# CCM_0010.net
KiCad netlist of a schematic drawn in EAGLE
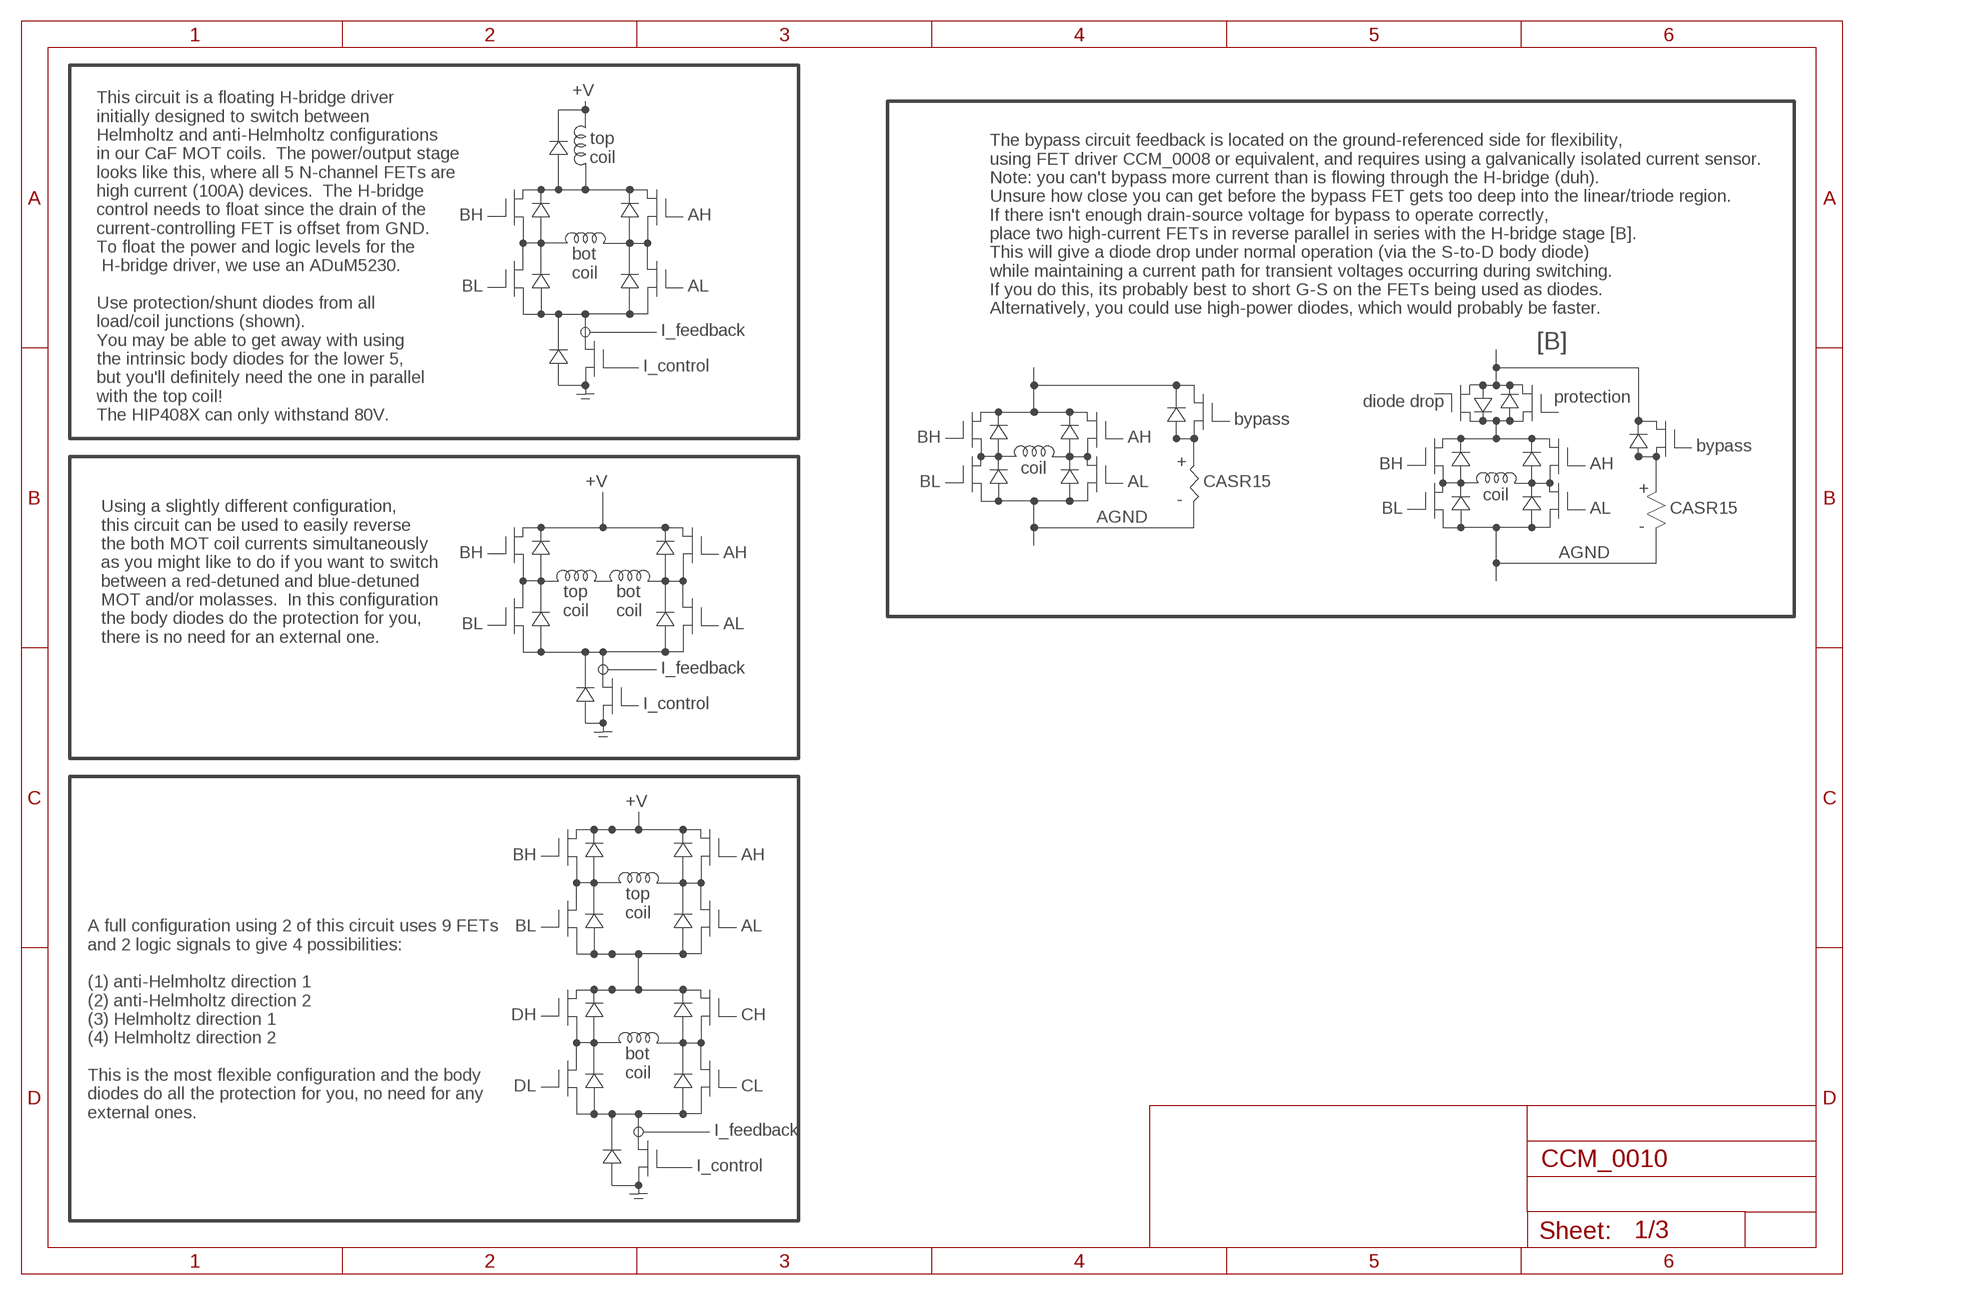
[diagram p0: schematic, sheet 1]
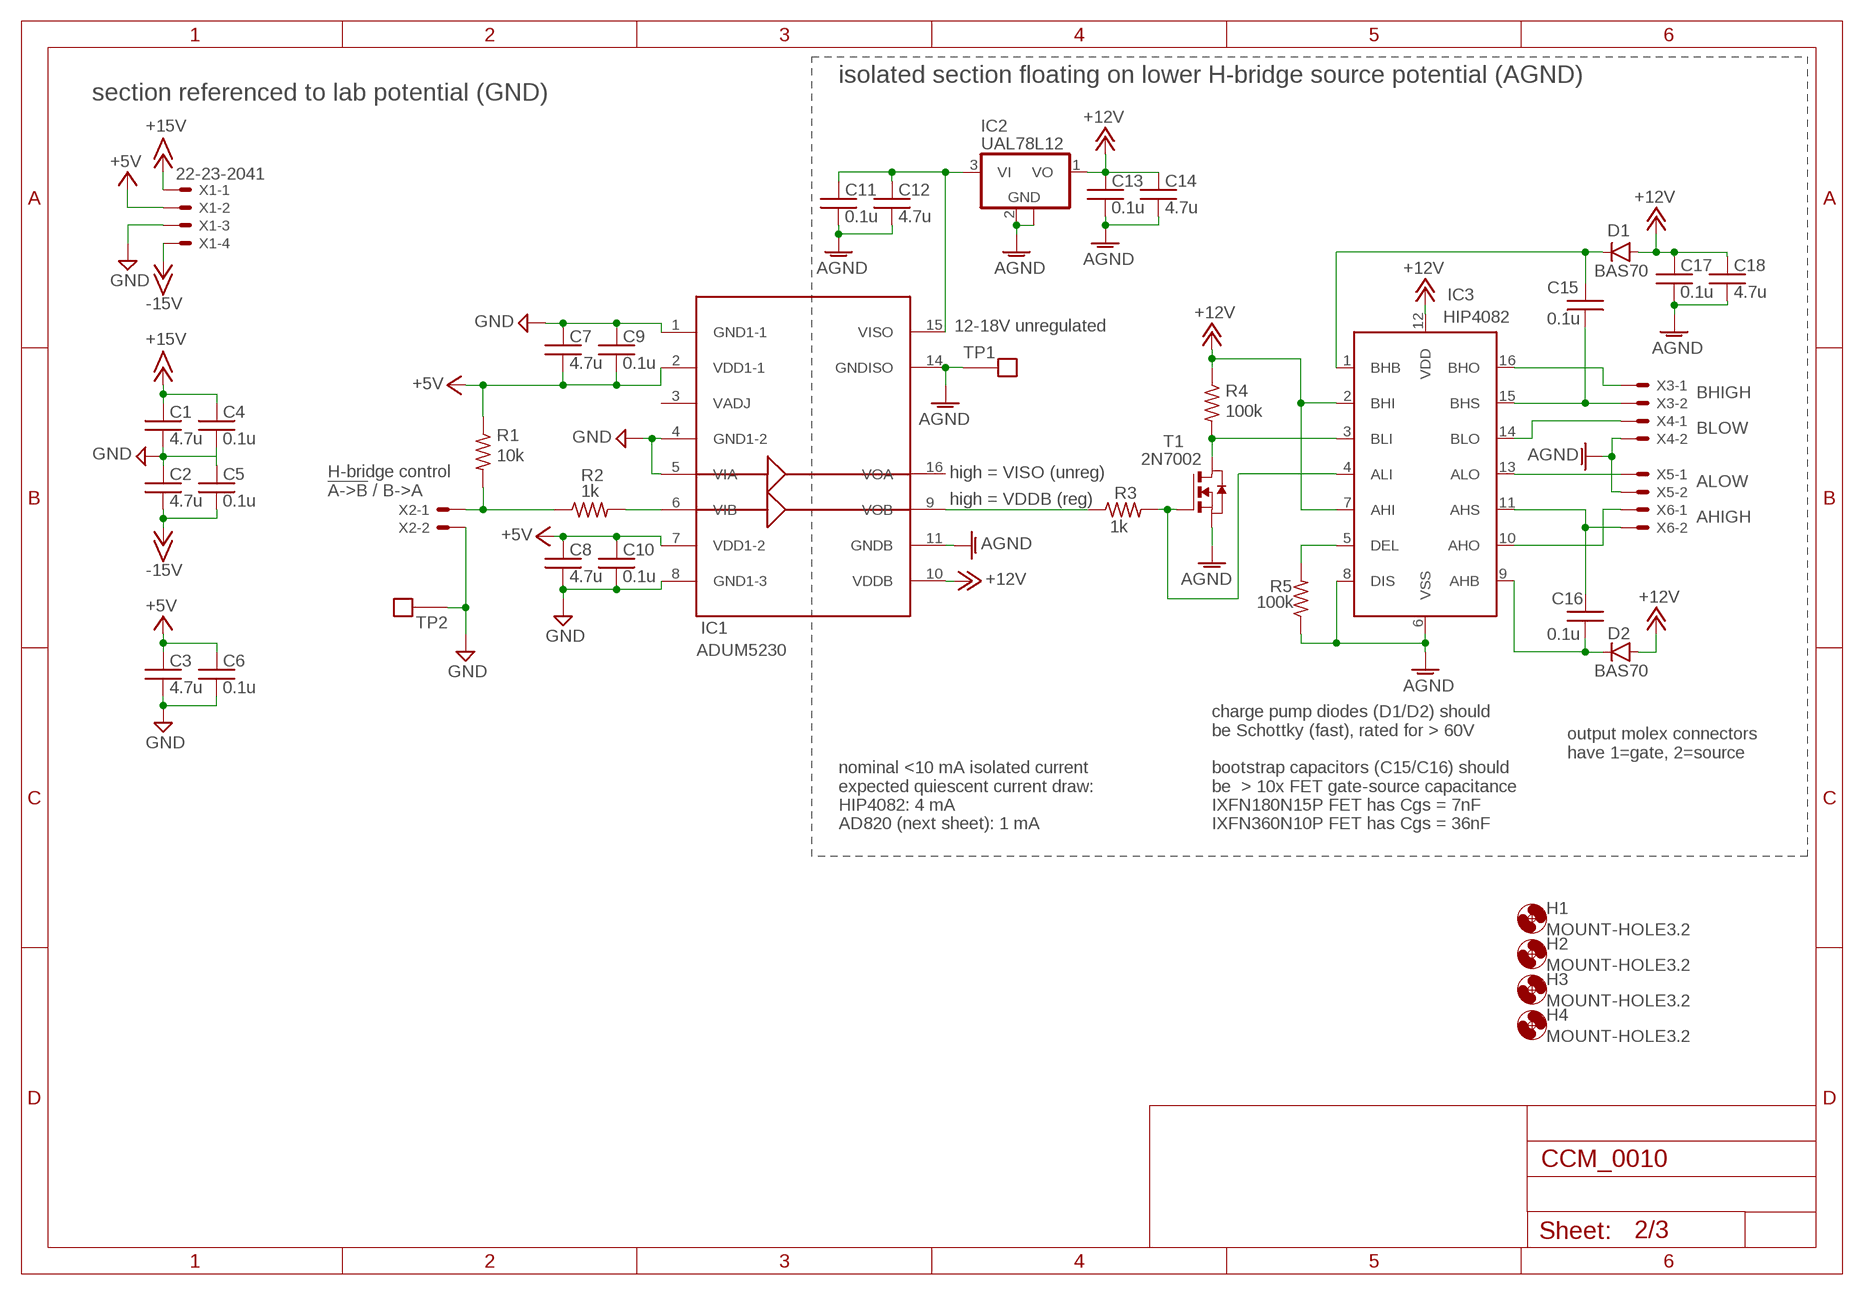
[diagram p1: schematic, sheet 2]
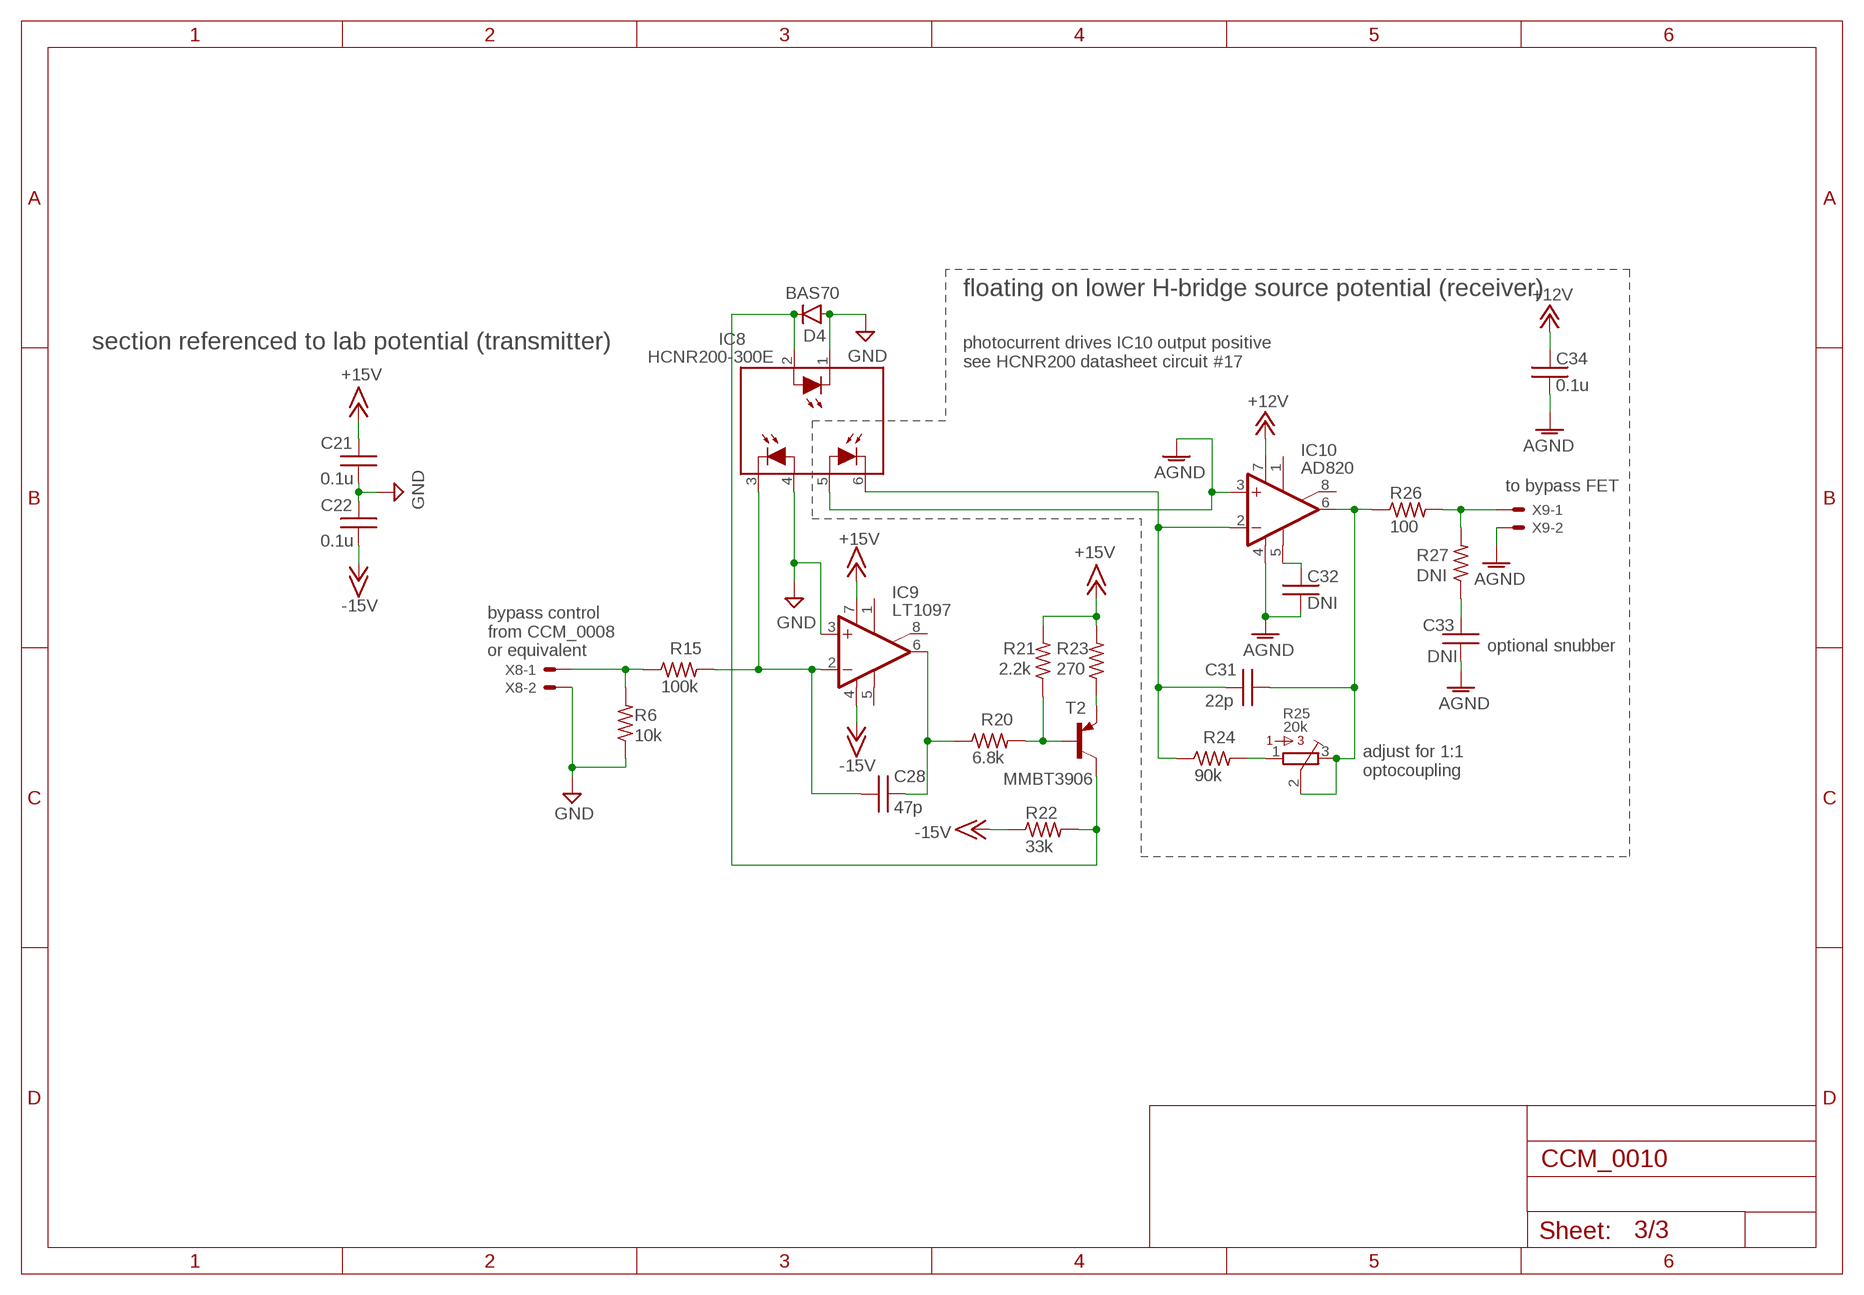
[diagram p2: schematic, sheet 3]

(export (version "E")
  (design (tool "Eeschema 10.0.6"))
  (components
    (comp (ref "C21")
      (value "0.1u")
      (footprint "eagle-import:0603")
      (libsource (lib "eagle-import") (part "C0603"))
    )
    (comp (ref "C22")
      (value "0.1u")
      (footprint "eagle-import:0603")
      (libsource (lib "eagle-import") (part "C0603"))
    )
    (comp (ref "C28")
      (value "47p")
      (footprint "eagle-import:0603")
      (libsource (lib "eagle-import") (part "C0603"))
    )
    (comp (ref "C31")
      (value "22p")
      (footprint "eagle-import:0603")
      (libsource (lib "eagle-import") (part "C0603"))
    )
    (comp (ref "C32")
      (value "DNI")
      (footprint "eagle-import:0603")
      (libsource (lib "eagle-import") (part "C0603"))
    )
    (comp (ref "C33")
      (value "DNI")
      (footprint "eagle-import:0603")
      (libsource (lib "eagle-import") (part "C0603"))
    )
    (comp (ref "C34")
      (value "0.1u")
      (footprint "eagle-import:0603")
      (libsource (lib "eagle-import") (part "C0603"))
    )
    (comp (ref "D4")
      (value "BAS70")
      (footprint "eagle-import:SOT23-3")
      (libsource (lib "eagle-import") (part "DIODESOT23"))
    )
    (comp (ref "IC8")
      (value "HCNR200-300E")
      (footprint "eagle-import:DIP8-400")
      (libsource (lib "eagle-import") (part "HCNR20-300E0"))
    )
    (comp (ref "IC9")
      (value "LT1097")
      (footprint "eagle-import:SO08")
      (libsource (lib "eagle-import") (part "OP07RC"))
    )
    (comp (ref "IC10")
      (value "AD820")
      (footprint "eagle-import:SO08")
      (libsource (lib "eagle-import") (part "OP07RC"))
    )
    (comp (ref "R6")
      (value "10k")
      (footprint "eagle-import:0603")
      (libsource (lib "eagle-import") (part "R0603"))
    )
    (comp (ref "R15")
      (value "100k")
      (footprint "eagle-import:0603")
      (libsource (lib "eagle-import") (part "R0603"))
    )
    (comp (ref "R20")
      (value "6.8k")
      (footprint "eagle-import:0603")
      (libsource (lib "eagle-import") (part "R0603"))
    )
    (comp (ref "R21")
      (value "2.2k")
      (footprint "eagle-import:0603")
      (libsource (lib "eagle-import") (part "R0603"))
    )
    (comp (ref "R22")
      (value "33k")
      (footprint "eagle-import:0603")
      (libsource (lib "eagle-import") (part "R0603"))
    )
    (comp (ref "R23")
      (value "270")
      (footprint "eagle-import:0603")
      (libsource (lib "eagle-import") (part "R0603"))
    )
    (comp (ref "R24")
      (value "90k")
      (footprint "eagle-import:0603")
      (libsource (lib "eagle-import") (part "R0603"))
    )
    (comp (ref "R25")
      (value "20k")
      (footprint "eagle-import:3386W")
      (libsource (lib "eagle-import") (part "3386-W"))
    )
    (comp (ref "R26")
      (value "100")
      (footprint "eagle-import:0603")
      (libsource (lib "eagle-import") (part "R0603"))
    )
    (comp (ref "R27")
      (value "DNI")
      (footprint "eagle-import:0603")
      (libsource (lib "eagle-import") (part "R0603"))
    )
    (comp (ref "T2")
      (value "MMBT3906")
      (footprint "eagle-import:SOT23-BEC")
      (libsource (lib "eagle-import") (part "-PNP-SOT23-BECMMBT3906LT1"))
    )
    (comp (ref "X8")
      (value "22-23-2021")
      (footprint "eagle-import:22-23-2021")
      (fields (field (name "MF") "MOLEX"))
      (libsource (lib "eagle-import") (part "22-23-2021"))
    )
    (comp (ref "X9")
      (value "22-23-2021")
      (footprint "eagle-import:22-23-2021")
      (fields (field (name "MF") "MOLEX"))
      (libsource (lib "eagle-import") (part "22-23-2021"))
    )
    (comp (ref "C1")
      (value "4.7u")
      (footprint "eagle-import:0603")
      (libsource (lib "eagle-import") (part "C0603"))
    )
    (comp (ref "C2")
      (value "4.7u")
      (footprint "eagle-import:0603")
      (libsource (lib "eagle-import") (part "C0603"))
    )
    (comp (ref "C3")
      (value "4.7u")
      (footprint "eagle-import:0603")
      (libsource (lib "eagle-import") (part "C0603"))
    )
    (comp (ref "C4")
      (value "0.1u")
      (footprint "eagle-import:0603")
      (libsource (lib "eagle-import") (part "C0603"))
    )
    (comp (ref "C5")
      (value "0.1u")
      (footprint "eagle-import:0603")
      (libsource (lib "eagle-import") (part "C0603"))
    )
    (comp (ref "C6")
      (value "0.1u")
      (footprint "eagle-import:0603")
      (libsource (lib "eagle-import") (part "C0603"))
    )
    (comp (ref "C7")
      (value "4.7u")
      (footprint "eagle-import:0603")
      (libsource (lib "eagle-import") (part "C0603"))
    )
    (comp (ref "C8")
      (value "4.7u")
      (footprint "eagle-import:0603")
      (libsource (lib "eagle-import") (part "C0603"))
    )
    (comp (ref "C9")
      (value "0.1u")
      (footprint "eagle-import:0603")
      (libsource (lib "eagle-import") (part "C0603"))
    )
    (comp (ref "C10")
      (value "0.1u")
      (footprint "eagle-import:0603")
      (libsource (lib "eagle-import") (part "C0603"))
    )
    (comp (ref "C11")
      (value "0.1u")
      (footprint "eagle-import:0603")
      (libsource (lib "eagle-import") (part "C0603"))
    )
    (comp (ref "C12")
      (value "4.7u")
      (footprint "eagle-import:0603")
      (libsource (lib "eagle-import") (part "C0603"))
    )
    (comp (ref "C13")
      (value "0.1u")
      (footprint "eagle-import:0603")
      (libsource (lib "eagle-import") (part "C0603"))
    )
    (comp (ref "C14")
      (value "4.7u")
      (footprint "eagle-import:0603")
      (libsource (lib "eagle-import") (part "C0603"))
    )
    (comp (ref "C15")
      (value "0.1u")
      (footprint "eagle-import:0603")
      (libsource (lib "eagle-import") (part "C0603"))
    )
    (comp (ref "C16")
      (value "0.1u")
      (footprint "eagle-import:0603")
      (libsource (lib "eagle-import") (part "C0603"))
    )
    (comp (ref "C17")
      (value "0.1u")
      (footprint "eagle-import:0603")
      (libsource (lib "eagle-import") (part "C0603"))
    )
    (comp (ref "C18")
      (value "4.7u")
      (footprint "eagle-import:0603")
      (libsource (lib "eagle-import") (part "C0603"))
    )
    (comp (ref "D1")
      (value "BAS70")
      (footprint "eagle-import:SOT23-3")
      (libsource (lib "eagle-import") (part "DIODESOT23"))
    )
    (comp (ref "D2")
      (value "BAS70")
      (footprint "eagle-import:SOT23-3")
      (libsource (lib "eagle-import") (part "DIODESOT23"))
    )
    (comp (ref "H1")
      (value "MOUNT-HOLE3.2")
      (footprint "eagle-import:3,2")
      (libsource (lib "eagle-import") (part "MOUNT-HOLE3.2"))
    )
    (comp (ref "H2")
      (value "MOUNT-HOLE3.2")
      (footprint "eagle-import:3,2")
      (libsource (lib "eagle-import") (part "MOUNT-HOLE3.2"))
    )
    (comp (ref "H3")
      (value "MOUNT-HOLE3.2")
      (footprint "eagle-import:3,2")
      (libsource (lib "eagle-import") (part "MOUNT-HOLE3.2"))
    )
    (comp (ref "H4")
      (value "MOUNT-HOLE3.2")
      (footprint "eagle-import:3,2")
      (libsource (lib "eagle-import") (part "MOUNT-HOLE3.2"))
    )
    (comp (ref "IC1")
      (value "ADUM5230")
      (footprint "eagle-import:SO16W")
      (libsource (lib "eagle-import") (part "ADUM5230"))
    )
    (comp (ref "IC2")
      (value "UAL78L12")
      (footprint "eagle-import:SOT89")
      (libsource (lib "eagle-import") (part "78LF12"))
    )
    (comp (ref "IC3")
      (value "HIP4082")
      (footprint "eagle-import:SO16")
      (libsource (lib "eagle-import") (part "HIP4082"))
    )
    (comp (ref "R1")
      (value "10k")
      (footprint "eagle-import:0603")
      (libsource (lib "eagle-import") (part "R0603"))
    )
    (comp (ref "R2")
      (value "1k")
      (footprint "eagle-import:0603")
      (libsource (lib "eagle-import") (part "R0603"))
    )
    (comp (ref "R3")
      (value "1k")
      (footprint "eagle-import:0603")
      (libsource (lib "eagle-import") (part "R0603"))
    )
    (comp (ref "R4")
      (value "100k")
      (footprint "eagle-import:0603")
      (libsource (lib "eagle-import") (part "R0603"))
    )
    (comp (ref "R5")
      (value "100k")
      (footprint "eagle-import:0603")
      (libsource (lib "eagle-import") (part "R0603"))
    )
    (comp (ref "T1")
      (value "2N7002")
      (footprint "eagle-import:SOT-23")
      (libsource (lib "eagle-import") (part "NMOSSOT23"))
    )
    (comp (ref "TP1")
      (value "TESTPOINT")
      (footprint "eagle-import:TESTPOINT")
      (libsource (lib "eagle-import") (part "TESTPOINT"))
    )
    (comp (ref "TP2")
      (value "TESTPOINT")
      (footprint "eagle-import:TESTPOINT")
      (libsource (lib "eagle-import") (part "TESTPOINT"))
    )
    (comp (ref "X1")
      (value "22-23-2041")
      (footprint "eagle-import:22-23-2041")
      (fields (field (name "MF") "MOLEX"))
      (libsource (lib "eagle-import") (part "22-23-2041"))
    )
    (comp (ref "X2")
      (value "22-23-2021")
      (footprint "eagle-import:22-23-2021")
      (fields (field (name "MF") "MOLEX"))
      (libsource (lib "eagle-import") (part "22-23-2021"))
    )
    (comp (ref "X3")
      (value "22-23-2021")
      (footprint "eagle-import:22-23-2021")
      (fields (field (name "MF") "MOLEX"))
      (libsource (lib "eagle-import") (part "22-23-2021"))
    )
    (comp (ref "X4")
      (value "22-23-2021")
      (footprint "eagle-import:22-23-2021")
      (fields (field (name "MF") "MOLEX"))
      (libsource (lib "eagle-import") (part "22-23-2021"))
    )
    (comp (ref "X5")
      (value "22-23-2021")
      (footprint "eagle-import:22-23-2021")
      (fields (field (name "MF") "MOLEX"))
      (libsource (lib "eagle-import") (part "22-23-2021"))
    )
    (comp (ref "X6")
      (value "22-23-2021")
      (footprint "eagle-import:22-23-2021")
      (fields (field (name "MF") "MOLEX"))
      (libsource (lib "eagle-import") (part "22-23-2021"))
    )
  )
  (nets
    (net (code "1") (name "+5V") (class "Default")
      (node (ref "C10") (pin "1") (pinfunction "1_1") (pintype "passive"))
      (node (ref "C3") (pin "1") (pinfunction "1_1") (pintype "passive"))
      (node (ref "C6") (pin "1") (pinfunction "1_1") (pintype "passive"))
      (node (ref "C7") (pin "2") (pinfunction "2_2") (pintype "passive"))
      (node (ref "C8") (pin "1") (pinfunction "1_1") (pintype "passive"))
      (node (ref "C9") (pin "2") (pinfunction "2_2") (pintype "passive"))
      (node (ref "IC1") (pin "2") (pinfunction "VDD1-1_2") (pintype "bidirectional"))
      (node (ref "IC1") (pin "7") (pinfunction "VDD1-2_7") (pintype "bidirectional"))
      (node (ref "R1") (pin "1") (pinfunction "1_1") (pintype "passive"))
      (node (ref "X1") (pin "2") (pinfunction "S_2") (pintype "passive"))
    )
    (net (code "2") (name "+12V") (class "Default")
      (node (ref "C13") (pin "1") (pinfunction "1_1") (pintype "passive"))
      (node (ref "C14") (pin "1") (pinfunction "1_1") (pintype "passive"))
      (node (ref "C17") (pin "1") (pinfunction "1_1") (pintype "passive"))
      (node (ref "C18") (pin "1") (pinfunction "1_1") (pintype "passive"))
      (node (ref "C34") (pin "1") (pinfunction "1_1") (pintype "passive"))
      (node (ref "D1") (pin "1") (pinfunction "A_1") (pintype "passive"))
      (node (ref "D2") (pin "1") (pinfunction "A_1") (pintype "passive"))
      (node (ref "IC1") (pin "10") (pinfunction "VDDB_10") (pintype "bidirectional"))
      (node (ref "IC10") (pin "7") (pinfunction "V+_7") (pintype "power_in"))
      (node (ref "IC2") (pin "1") (pinfunction "VO_1") (pintype "passive"))
      (node (ref "IC3") (pin "12") (pinfunction "VDD_12") (pintype "power_in"))
      (node (ref "IC3") (pin "2") (pinfunction "BHI_2") (pintype "input"))
      (node (ref "IC3") (pin "7") (pinfunction "AHI_7") (pintype "input"))
      (node (ref "R4") (pin "1") (pinfunction "1_1") (pintype "passive"))
    )
    (net (code "3") (name "+15V") (class "Default")
      (node (ref "C1") (pin "1") (pinfunction "1_1") (pintype "passive"))
      (node (ref "C21") (pin "2") (pinfunction "2_2") (pintype "passive"))
      (node (ref "C4") (pin "1") (pinfunction "1_1") (pintype "passive"))
      (node (ref "IC9") (pin "7") (pinfunction "V+_7") (pintype "power_in"))
      (node (ref "R21") (pin "2") (pinfunction "2_2") (pintype "passive"))
      (node (ref "R23") (pin "2") (pinfunction "2_2") (pintype "passive"))
      (node (ref "X1") (pin "1") (pinfunction "S_1") (pintype "passive"))
    )
    (net (code "4") (name "-15V") (class "Default")
      (node (ref "C2") (pin "2") (pinfunction "2_2") (pintype "passive"))
      (node (ref "C22") (pin "1") (pinfunction "1_1") (pintype "passive"))
      (node (ref "C5") (pin "2") (pinfunction "2_2") (pintype "passive"))
      (node (ref "IC9") (pin "4") (pinfunction "V-_4") (pintype "power_in"))
      (node (ref "R22") (pin "1") (pinfunction "1_1") (pintype "passive"))
      (node (ref "X1") (pin "4") (pinfunction "S_4") (pintype "passive"))
    )
    (net (code "5") (name "AGND") (class "Default")
      (node (ref "C11") (pin "2") (pinfunction "2_2") (pintype "passive"))
      (node (ref "C12") (pin "2") (pinfunction "2_2") (pintype "passive"))
      (node (ref "C13") (pin "2") (pinfunction "2_2") (pintype "passive"))
      (node (ref "C14") (pin "2") (pinfunction "2_2") (pintype "passive"))
      (node (ref "C17") (pin "2") (pinfunction "2_2") (pintype "passive"))
      (node (ref "C18") (pin "2") (pinfunction "2_2") (pintype "passive"))
      (node (ref "C32") (pin "2") (pinfunction "2_2") (pintype "passive"))
      (node (ref "C33") (pin "2") (pinfunction "2_2") (pintype "passive"))
      (node (ref "C34") (pin "2") (pinfunction "2_2") (pintype "passive"))
      (node (ref "IC1") (pin "11") (pinfunction "GNDB_11") (pintype "bidirectional"))
      (node (ref "IC1") (pin "14") (pinfunction "GNDISO_14") (pintype "bidirectional"))
      (node (ref "IC10") (pin "3") (pinfunction "+IN_3") (pintype "input"))
      (node (ref "IC10") (pin "4") (pinfunction "V-_4") (pintype "power_in"))
      (node (ref "IC2") (pin "2") (pinfunction "GND_2") (pintype "passive"))
      (node (ref "IC2") (pin "2@1") (pinfunction "GND_2@1") (pintype "passive"))
      (node (ref "IC3") (pin "6") (pinfunction "VSS_6") (pintype "power_in"))
      (node (ref "IC3") (pin "8") (pinfunction "DIS_8") (pintype "input"))
      (node (ref "IC8") (pin "5") (pinfunction "A2_5") (pintype "passive"))
      (node (ref "R5") (pin "1") (pinfunction "1_1") (pintype "passive"))
      (node (ref "T1") (pin "2") (pinfunction "S_2") (pintype "passive"))
      (node (ref "TP1") (pin "P$1") (pinfunction "P$1_P$1") (pintype "bidirectional"))
      (node (ref "X4") (pin "2") (pinfunction "S_2") (pintype "passive"))
      (node (ref "X5") (pin "2") (pinfunction "S_2") (pintype "passive"))
      (node (ref "X9") (pin "2") (pinfunction "S_2") (pintype "passive"))
    )
    (net (code "6") (name "GND") (class "Default")
      (node (ref "C1") (pin "2") (pinfunction "2_2") (pintype "passive"))
      (node (ref "C10") (pin "2") (pinfunction "2_2") (pintype "passive"))
      (node (ref "C2") (pin "1") (pinfunction "1_1") (pintype "passive"))
      (node (ref "C21") (pin "1") (pinfunction "1_1") (pintype "passive"))
      (node (ref "C22") (pin "2") (pinfunction "2_2") (pintype "passive"))
      (node (ref "C3") (pin "2") (pinfunction "2_2") (pintype "passive"))
      (node (ref "C4") (pin "2") (pinfunction "2_2") (pintype "passive"))
      (node (ref "C5") (pin "1") (pinfunction "1_1") (pintype "passive"))
      (node (ref "C6") (pin "2") (pinfunction "2_2") (pintype "passive"))
      (node (ref "C7") (pin "1") (pinfunction "1_1") (pintype "passive"))
      (node (ref "C8") (pin "2") (pinfunction "2_2") (pintype "passive"))
      (node (ref "C9") (pin "1") (pinfunction "1_1") (pintype "passive"))
      (node (ref "D4") (pin "1") (pinfunction "A_1") (pintype "passive"))
      (node (ref "IC1") (pin "1") (pinfunction "GND1-1_1") (pintype "bidirectional"))
      (node (ref "IC1") (pin "4") (pinfunction "GND1-2_4") (pintype "bidirectional"))
      (node (ref "IC1") (pin "5") (pinfunction "VIA_5") (pintype "bidirectional"))
      (node (ref "IC1") (pin "8") (pinfunction "GND1-3_8") (pintype "bidirectional"))
      (node (ref "IC8") (pin "1") (pinfunction "C_1") (pintype "passive"))
      (node (ref "IC8") (pin "4") (pinfunction "A1_4") (pintype "passive"))
      (node (ref "IC9") (pin "3") (pinfunction "+IN_3") (pintype "input"))
      (node (ref "R6") (pin "1") (pinfunction "1_1") (pintype "passive"))
      (node (ref "TP2") (pin "P$1") (pinfunction "P$1_P$1") (pintype "bidirectional"))
      (node (ref "X1") (pin "3") (pinfunction "S_3") (pintype "passive"))
      (node (ref "X2") (pin "2") (pinfunction "S_2") (pintype "passive"))
      (node (ref "X8") (pin "2") (pinfunction "S_2") (pintype "passive"))
    )
    (net (code "7") (name "Net-(C33-Pad1)") (class "Default")
      (node (ref "C33") (pin "1") (pinfunction "1_1") (pintype "passive"))
      (node (ref "R27") (pin "1") (pinfunction "1_1") (pintype "passive"))
    )
    (net (code "8") (name "Net-(D1-C)") (class "Default")
      (node (ref "C15") (pin "2") (pinfunction "2_2") (pintype "passive"))
      (node (ref "D1") (pin "3") (pinfunction "C_3") (pintype "passive"))
      (node (ref "IC3") (pin "1") (pinfunction "BHB_1") (pintype "input"))
    )
    (net (code "9") (name "Net-(D2-C)") (class "Default")
      (node (ref "C16") (pin "1") (pinfunction "1_1") (pintype "passive"))
      (node (ref "D2") (pin "3") (pinfunction "C_3") (pintype "passive"))
      (node (ref "IC3") (pin "9") (pinfunction "AHB_9") (pintype "output"))
    )
    (net (code "10") (name "Net-(D4-C)") (class "Default")
      (node (ref "D4") (pin "3") (pinfunction "C_3") (pintype "passive"))
      (node (ref "IC8") (pin "2") (pinfunction "A_2") (pintype "passive"))
      (node (ref "R22") (pin "2") (pinfunction "2_2") (pintype "passive"))
      (node (ref "T2") (pin "C") (pinfunction "C_C") (pintype "passive"))
    )
    (net (code "11") (name "Net-(IC1-VIB)") (class "Default")
      (node (ref "IC1") (pin "6") (pinfunction "VIB_6") (pintype "bidirectional"))
      (node (ref "R2") (pin "2") (pinfunction "2_2") (pintype "passive"))
    )
    (net (code "12") (name "Net-(IC1-VISO)") (class "Default")
      (node (ref "C11") (pin "1") (pinfunction "1_1") (pintype "passive"))
      (node (ref "C12") (pin "1") (pinfunction "1_1") (pintype "passive"))
      (node (ref "IC1") (pin "15") (pinfunction "VISO_15") (pintype "bidirectional"))
      (node (ref "IC2") (pin "3") (pinfunction "VI_3") (pintype "input"))
    )
    (net (code "13") (name "Net-(IC1-VOB)") (class "Default")
      (node (ref "IC1") (pin "9") (pinfunction "VOB_9") (pintype "bidirectional"))
      (node (ref "R3") (pin "1") (pinfunction "1_1") (pintype "passive"))
    )
    (net (code "14") (name "Net-(IC3-AHO)") (class "Default")
      (node (ref "IC3") (pin "10") (pinfunction "AHO_10") (pintype "input"))
      (node (ref "X6") (pin "1") (pinfunction "S_1") (pintype "passive"))
    )
    (net (code "15") (name "Net-(IC3-AHS)") (class "Default")
      (node (ref "C16") (pin "2") (pinfunction "2_2") (pintype "passive"))
      (node (ref "IC3") (pin "11") (pinfunction "AHS_11") (pintype "output"))
      (node (ref "X6") (pin "2") (pinfunction "S_2") (pintype "passive"))
    )
    (net (code "16") (name "Net-(IC3-ALI)") (class "Default")
      (node (ref "IC3") (pin "4") (pinfunction "ALI_4") (pintype "input"))
      (node (ref "R3") (pin "2") (pinfunction "2_2") (pintype "passive"))
      (node (ref "T1") (pin "3") (pinfunction "G_3") (pintype "passive"))
    )
    (net (code "17") (name "Net-(IC3-ALO)") (class "Default")
      (node (ref "IC3") (pin "13") (pinfunction "ALO_13") (pintype "passive"))
      (node (ref "X5") (pin "1") (pinfunction "S_1") (pintype "passive"))
    )
    (net (code "18") (name "Net-(IC3-BHO)") (class "Default")
      (node (ref "IC3") (pin "16") (pinfunction "BHO_16") (pintype "output"))
      (node (ref "X3") (pin "1") (pinfunction "S_1") (pintype "passive"))
    )
    (net (code "19") (name "Net-(IC3-BHS)") (class "Default")
      (node (ref "C15") (pin "1") (pinfunction "1_1") (pintype "passive"))
      (node (ref "IC3") (pin "15") (pinfunction "BHS_15") (pintype "input"))
      (node (ref "X3") (pin "2") (pinfunction "S_2") (pintype "passive"))
    )
    (net (code "20") (name "Net-(IC3-BLI)") (class "Default")
      (node (ref "IC3") (pin "3") (pinfunction "BLI_3") (pintype "input"))
      (node (ref "R4") (pin "2") (pinfunction "2_2") (pintype "passive"))
      (node (ref "T1") (pin "1") (pinfunction "D_1") (pintype "passive"))
    )
    (net (code "21") (name "Net-(IC3-BLO)") (class "Default")
      (node (ref "IC3") (pin "14") (pinfunction "BLO_14") (pintype "output"))
      (node (ref "X4") (pin "1") (pinfunction "S_1") (pintype "passive"))
    )
    (net (code "22") (name "Net-(IC3-DEL)") (class "Default")
      (node (ref "IC3") (pin "5") (pinfunction "DEL_5") (pintype "input"))
      (node (ref "R5") (pin "2") (pinfunction "2_2") (pintype "passive"))
    )
    (net (code "23") (name "Net-(IC8-C1)") (class "Default")
      (node (ref "C28") (pin "2") (pinfunction "2_2") (pintype "passive"))
      (node (ref "IC8") (pin "3") (pinfunction "C1_3") (pintype "passive"))
      (node (ref "IC9") (pin "2") (pinfunction "-IN_2") (pintype "input"))
      (node (ref "R15") (pin "2") (pinfunction "2_2") (pintype "passive"))
    )
    (net (code "24") (name "Net-(IC9-OUT)") (class "Default")
      (node (ref "C28") (pin "1") (pinfunction "1_1") (pintype "passive"))
      (node (ref "IC9") (pin "6") (pinfunction "OUT_6") (pintype "output"))
      (node (ref "R20") (pin "1") (pinfunction "1_1") (pintype "passive"))
    )
    (net (code "25") (name "Net-(IC10--IN)") (class "Default")
      (node (ref "C31") (pin "2") (pinfunction "2_2") (pintype "passive"))
      (node (ref "IC10") (pin "2") (pinfunction "-IN_2") (pintype "input"))
      (node (ref "IC8") (pin "6") (pinfunction "C2_6") (pintype "passive"))
      (node (ref "R24") (pin "1") (pinfunction "1_1") (pintype "passive"))
    )
    (net (code "26") (name "Net-(IC10-OPT)") (class "Default")
      (node (ref "C32") (pin "1") (pinfunction "1_1") (pintype "passive"))
      (node (ref "IC10") (pin "5") (pinfunction "OPT_5") (pintype "passive"))
    )
    (net (code "27") (name "Net-(IC10-OUT)") (class "Default")
      (node (ref "C31") (pin "1") (pinfunction "1_1") (pintype "passive"))
      (node (ref "IC10") (pin "6") (pinfunction "OUT_6") (pintype "output"))
      (node (ref "R25") (pin "2") (pinfunction "2_2") (pintype "passive"))
      (node (ref "R25") (pin "3") (pinfunction "3_3") (pintype "passive"))
      (node (ref "R26") (pin "1") (pinfunction "1_1") (pintype "passive"))
    )
    (net (code "28") (name "Net-(R20-Pad2)") (class "Default")
      (node (ref "R20") (pin "2") (pinfunction "2_2") (pintype "passive"))
      (node (ref "R21") (pin "1") (pinfunction "1_1") (pintype "passive"))
      (node (ref "T2") (pin "B") (pinfunction "B_B") (pintype "passive"))
    )
    (net (code "29") (name "Net-(R23-Pad1)") (class "Default")
      (node (ref "R23") (pin "1") (pinfunction "1_1") (pintype "passive"))
      (node (ref "T2") (pin "E") (pinfunction "E_E") (pintype "passive"))
    )
    (net (code "30") (name "Net-(R24-Pad2)") (class "Default")
      (node (ref "R24") (pin "2") (pinfunction "2_2") (pintype "passive"))
      (node (ref "R25") (pin "1") (pinfunction "1_1") (pintype "passive"))
    )
    (net (code "31") (name "Net-(X2A-S)") (class "Default")
      (node (ref "R1") (pin "2") (pinfunction "2_2") (pintype "passive"))
      (node (ref "R2") (pin "1") (pinfunction "1_1") (pintype "passive"))
      (node (ref "X2") (pin "1") (pinfunction "S_1") (pintype "passive"))
    )
    (net (code "32") (name "Net-(X8A-S)") (class "Default")
      (node (ref "R15") (pin "1") (pinfunction "1_1") (pintype "passive"))
      (node (ref "R6") (pin "2") (pinfunction "2_2") (pintype "passive"))
      (node (ref "X8") (pin "1") (pinfunction "S_1") (pintype "passive"))
    )
    (net (code "33") (name "Net-(X9A-S)") (class "Default")
      (node (ref "R26") (pin "2") (pinfunction "2_2") (pintype "passive"))
      (node (ref "R27") (pin "2") (pinfunction "2_2") (pintype "passive"))
      (node (ref "X9") (pin "1") (pinfunction "S_1") (pintype "passive"))
    )
    (net (code "34") (name "unconnected-(IC1-VADJ-Pad3)") (class "Default")
      (node (ref "IC1") (pin "3") (pinfunction "VADJ_3") (pintype "bidirectional"))
    )
    (net (code "35") (name "unconnected-(IC1-VOA-Pad16)") (class "Default")
      (node (ref "IC1") (pin "16") (pinfunction "VOA_16") (pintype "bidirectional"))
    )
    (net (code "36") (name "unconnected-(IC9-ON1-Pad1)") (class "Default")
      (node (ref "IC9") (pin "1") (pinfunction "ON1_1") (pintype "passive"))
    )
    (net (code "37") (name "unconnected-(IC9-ON2-Pad8)") (class "Default")
      (node (ref "IC9") (pin "8") (pinfunction "ON2_8") (pintype "passive"))
    )
    (net (code "38") (name "unconnected-(IC9-OPT-Pad5)") (class "Default")
      (node (ref "IC9") (pin "5") (pinfunction "OPT_5") (pintype "passive"))
    )
    (net (code "39") (name "unconnected-(IC10-ON1-Pad1)") (class "Default")
      (node (ref "IC10") (pin "1") (pinfunction "ON1_1") (pintype "passive"))
    )
    (net (code "40") (name "unconnected-(IC10-ON2-Pad8)") (class "Default")
      (node (ref "IC10") (pin "8") (pinfunction "ON2_8") (pintype "passive"))
    )
  )
)
